# SWD_v1_0.net
KiCad netlist of a schematic drawn in Altium Designer
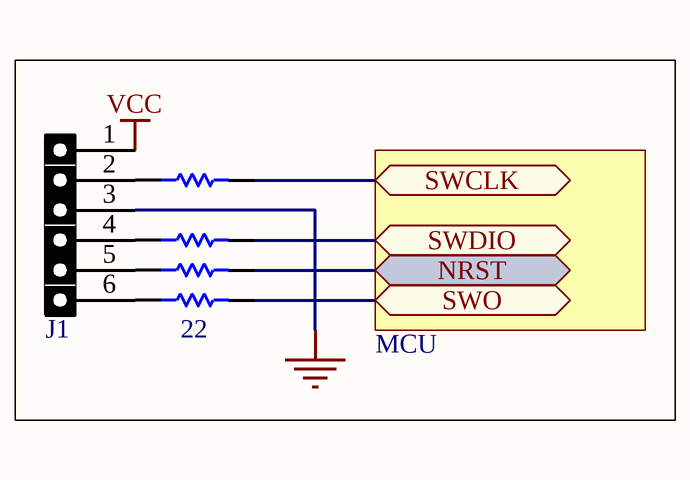
[diagram p0: SWD_v1.0.SchDoc]

(export (version "E")
  (design (tool "Eeschema 10.0.6"))
  (components
    (comp (ref "J1")
      (value "Connector_1x6Pin_Female")
      (footprint "HEADER_THD_STAND_FEMALE_1X6")
      (description "Connector, Header, 6Pin")
      (libsource (lib "Connector") (part "Connector_1x6Pin_Female"))
    )
    (comp (ref "R1")
      (value "22")
      (footprint "SMD_0805")
      (description "Resistor, 1/4W, 5%")
      (libsource (lib "General") (part "Resistor"))
    )
    (comp (ref "R2")
      (value "22")
      (footprint "SMD_0805")
      (description "Resistor, 1/4W, 5%")
      (libsource (lib "General") (part "Resistor"))
    )
    (comp (ref "R3")
      (value "22")
      (footprint "SMD_0805")
      (description "Resistor, 1/4W, 5%")
      (libsource (lib "General") (part "Resistor"))
    )
    (comp (ref "R4")
      (value "22")
      (footprint "SMD_0805")
      (description "Resistor, 1/4W, 5%")
      (libsource (lib "General") (part "Resistor"))
    )
  )
  (nets
    (net (code "1") (name "/NRST") (class "Default")
      (node (ref "R3") (pin "1") (pinfunction "1_1") (pintype "passive"))
    )
    (net (code "2") (name "/SWCLK") (class "Default")
      (node (ref "R1") (pin "1") (pinfunction "1_1") (pintype "passive"))
    )
    (net (code "3") (name "/SWDIO") (class "Default")
      (node (ref "R2") (pin "1") (pinfunction "1_1") (pintype "passive"))
    )
    (net (code "4") (name "/SWO") (class "Default")
      (node (ref "R4") (pin "1") (pinfunction "1_1") (pintype "passive"))
    )
    (net (code "5") (name "GND") (class "Default")
      (node (ref "J1") (pin "3") (pinfunction "3_3") (pintype "passive"))
    )
    (net (code "6") (name "Net-(J1-Pad2)") (class "Default")
      (node (ref "J1") (pin "2") (pinfunction "2_2") (pintype "passive"))
      (node (ref "R1") (pin "2") (pinfunction "2_2") (pintype "passive"))
    )
    (net (code "7") (name "Net-(J1-Pad4)") (class "Default")
      (node (ref "J1") (pin "4") (pinfunction "4_4") (pintype "passive"))
      (node (ref "R2") (pin "2") (pinfunction "2_2") (pintype "passive"))
    )
    (net (code "8") (name "Net-(J1-Pad5)") (class "Default")
      (node (ref "J1") (pin "5") (pinfunction "5_5") (pintype "passive"))
      (node (ref "R3") (pin "2") (pinfunction "2_2") (pintype "passive"))
    )
    (net (code "9") (name "Net-(J1-Pad6)") (class "Default")
      (node (ref "J1") (pin "6") (pinfunction "6_6") (pintype "passive"))
      (node (ref "R4") (pin "2") (pinfunction "2_2") (pintype "passive"))
    )
    (net (code "10") (name "VCC") (class "Default")
      (node (ref "J1") (pin "1") (pinfunction "1_1") (pintype "passive"))
    )
  )
)
